# msp430g2432_uC_Module.net
KiCad netlist of a schematic drawn in EAGLE
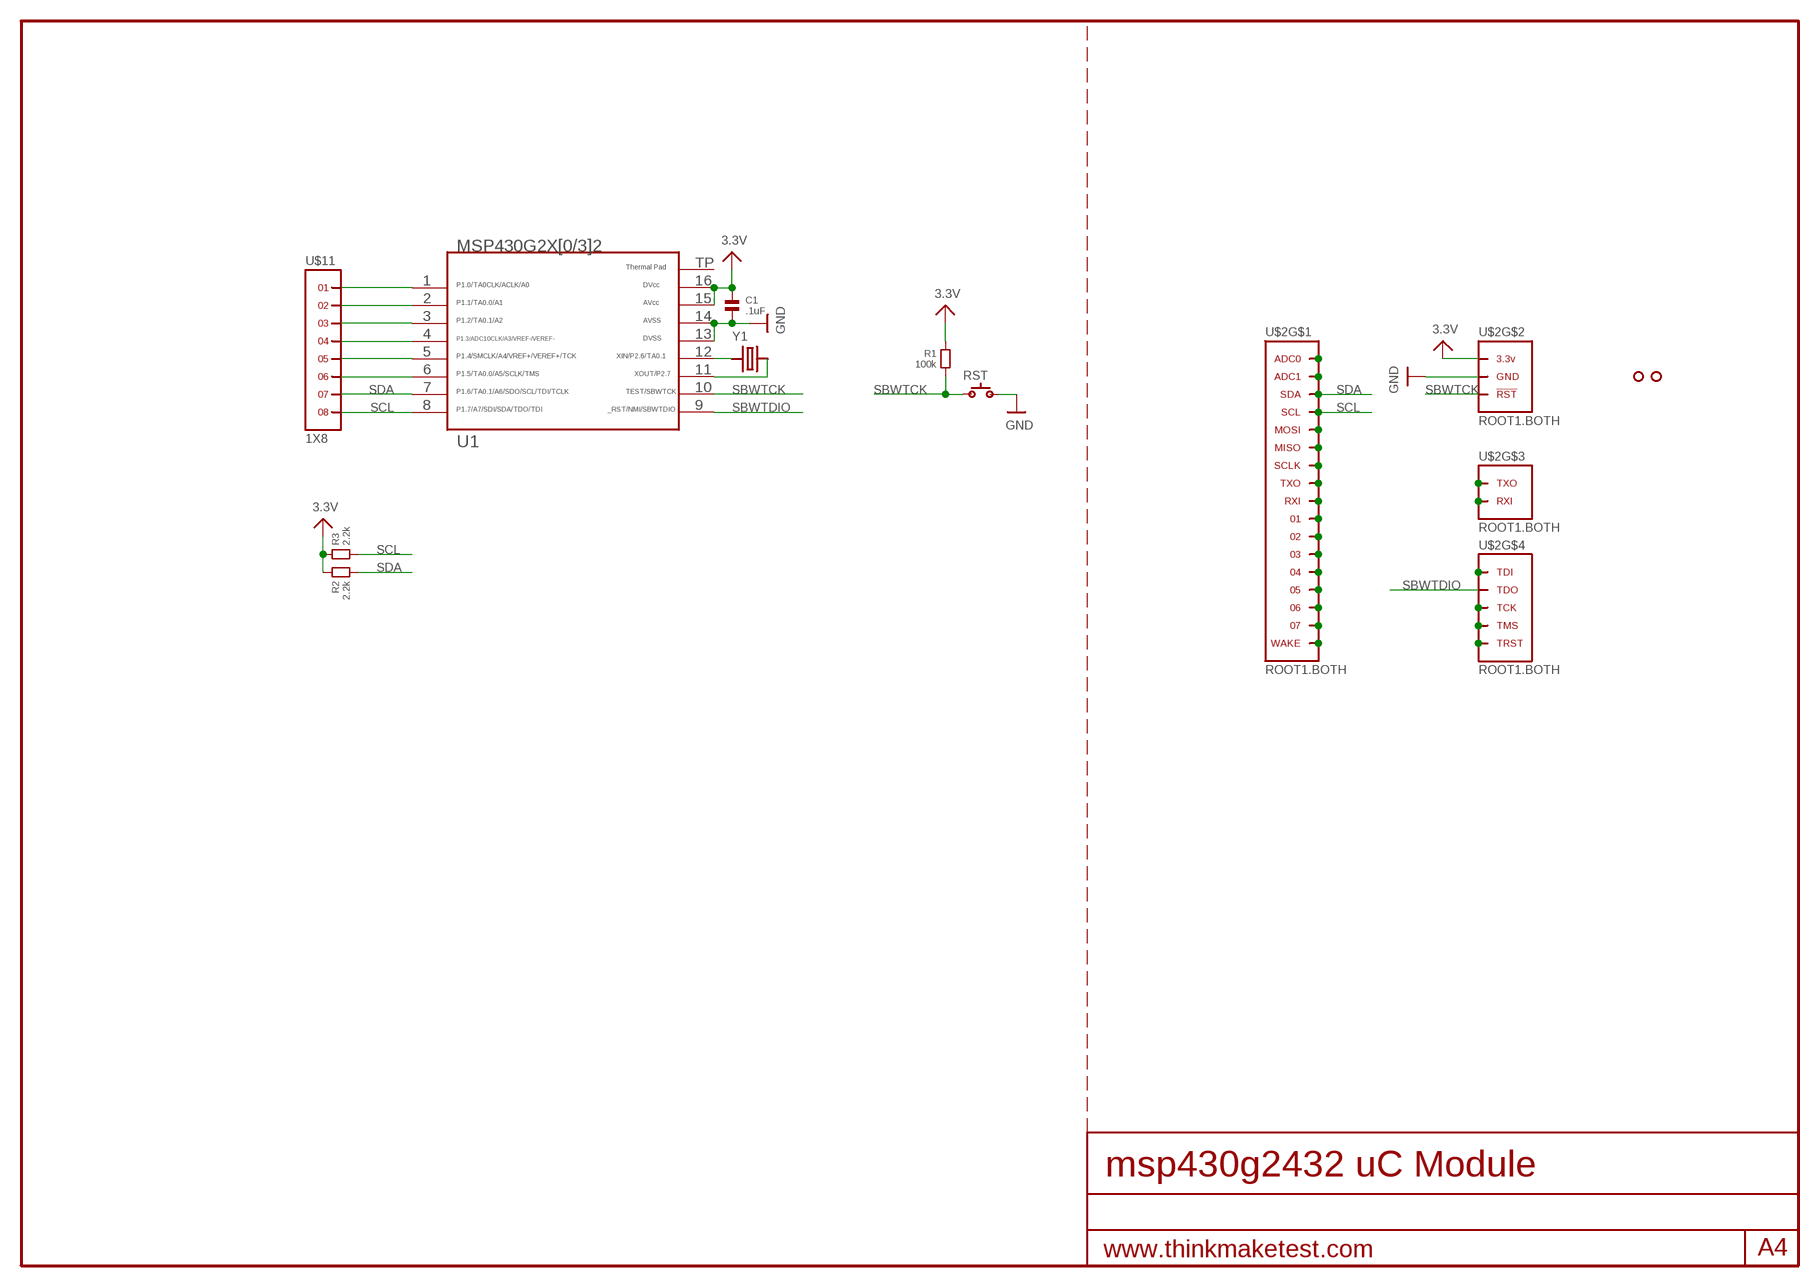
[diagram p0: schematic, sheet 1]

(export (version "E")
  (design (tool "Eeschema 10.0.6"))
  (components
    (comp (ref "C1")
      (value ".1uF")
      (footprint "eagle-import:0603")
      (libsource (lib "eagle-import") (part "CAPACITOR.0603"))
    )
    (comp (ref "R1")
      (value "100k")
      (footprint "eagle-import:0603")
      (libsource (lib "eagle-import") (part "RESISTOR.0603"))
    )
    (comp (ref "R2")
      (value "2.2k")
      (footprint "eagle-import:0603")
      (libsource (lib "eagle-import") (part "RESISTOR.0603"))
    )
    (comp (ref "R3")
      (value "2.2k")
      (footprint "eagle-import:0603")
      (libsource (lib "eagle-import") (part "RESISTOR.0603"))
    )
    (comp (ref "RST")
      (value "SPST.B3U-3000P(M)-B")
      (footprint "eagle-import:B3U-3000P(M)-B")
      (libsource (lib "eagle-import") (part "SPST.B3U-3000P(M)-B"))
    )
    (comp (ref "U$2")
      (value "ROOT1.BOTH")
      (footprint "eagle-import:ROOT1.BOTH")
      (libsource (lib "eagle-import") (part "ROOT1.BOTH"))
    )
    (comp (ref "U$3")
      (value "HOLE.2MM")
      (footprint "eagle-import:2MM")
      (libsource (lib "eagle-import") (part "HOLE.2MM"))
    )
    (comp (ref "U$4")
      (value "HOLE.2MM")
      (footprint "eagle-import:2MM")
      (libsource (lib "eagle-import") (part "HOLE.2MM"))
    )
    (comp (ref "U$11")
      (value "1X8")
      (footprint "eagle-import:1X8")
      (libsource (lib "eagle-import") (part "1X8"))
    )
    (comp (ref "U1")
      (value "G2432.QFN16")
      (footprint "eagle-import:RSA16")
      (libsource (lib "eagle-import") (part "G2X[0/3]2---RSA16"))
    )
    (comp (ref "Y1")
      (value "CRYSTAL.ABS07")
      (footprint "eagle-import:ABS07")
      (libsource (lib "eagle-import") (part "CRYSTAL.ABS07"))
    )
  )
  (nets
    (net (code "1") (name "/SBWTCK") (class "Default")
      (node (ref "R1") (pin "2") (pinfunction "2_2") (pintype "bidirectional"))
      (node (ref "RST") (pin "2") (pinfunction "2_2") (pintype "bidirectional"))
      (node (ref "U$2") (pin "RST") (pinfunction "~{RST}_RST") (pintype "bidirectional"))
      (node (ref "U$2") (pin "RST@1") (pinfunction "~{RST}_RST@1") (pintype "bidirectional"))
      (node (ref "U$2") (pin "RST@VIA") (pinfunction "~{RST}_RST@VIA") (pintype "bidirectional"))
      (node (ref "U1") (pin "10") (pinfunction "10_10") (pintype "bidirectional"))
    )
    (net (code "2") (name "/SBWTDIO") (class "Default")
      (node (ref "U$2") (pin "TDO") (pinfunction "TDO_TDO") (pintype "bidirectional"))
      (node (ref "U$2") (pin "TDO@1") (pinfunction "TDO_TDO@1") (pintype "bidirectional"))
      (node (ref "U$2") (pin "TDO@VIA") (pinfunction "TDO_TDO@VIA") (pintype "bidirectional"))
      (node (ref "U1") (pin "9") (pinfunction "9_9") (pintype "bidirectional"))
    )
    (net (code "3") (name "/SCL") (class "Default")
      (node (ref "R3") (pin "2") (pinfunction "2_2") (pintype "bidirectional"))
      (node (ref "U$11") (pin "8") (pinfunction "8_8") (pintype "bidirectional"))
      (node (ref "U$2") (pin "SCL") (pinfunction "SCL_SCL") (pintype "bidirectional"))
      (node (ref "U$2") (pin "SCL@1") (pinfunction "SCL_SCL@1") (pintype "bidirectional"))
      (node (ref "U$2") (pin "SCL@VIA") (pinfunction "SCL_SCL@VIA") (pintype "bidirectional"))
      (node (ref "U1") (pin "8") (pinfunction "8_8") (pintype "bidirectional"))
    )
    (net (code "4") (name "/SDA") (class "Default")
      (node (ref "R2") (pin "2") (pinfunction "2_2") (pintype "bidirectional"))
      (node (ref "U$11") (pin "7") (pinfunction "7_7") (pintype "bidirectional"))
      (node (ref "U$2") (pin "SDA") (pinfunction "SDA_SDA") (pintype "bidirectional"))
      (node (ref "U$2") (pin "SDA@1") (pinfunction "SDA_SDA@1") (pintype "bidirectional"))
      (node (ref "U$2") (pin "SDA@VIA") (pinfunction "SDA_SDA@VIA") (pintype "bidirectional"))
      (node (ref "U1") (pin "7") (pinfunction "7_7") (pintype "bidirectional"))
    )
    (net (code "5") (name "3.3V") (class "Default")
      (node (ref "C1") (pin "1") (pinfunction "1_1") (pintype "bidirectional"))
      (node (ref "R1") (pin "1") (pinfunction "1_1") (pintype "bidirectional"))
      (node (ref "R2") (pin "1") (pinfunction "1_1") (pintype "bidirectional"))
      (node (ref "R3") (pin "1") (pinfunction "1_1") (pintype "bidirectional"))
      (node (ref "U$2") (pin "3.3V@1") (pinfunction "3.3V_3.3V@1") (pintype "bidirectional"))
      (node (ref "U$2") (pin "3.3V@10") (pinfunction "3.3V_3.3V@10") (pintype "bidirectional"))
      (node (ref "U$2") (pin "3.3V@11") (pinfunction "3.3V_3.3V@11") (pintype "bidirectional"))
      (node (ref "U$2") (pin "3.3V@12") (pinfunction "3.3V_3.3V@12") (pintype "bidirectional"))
      (node (ref "U$2") (pin "3.3V@13") (pinfunction "3.3V_3.3V@13") (pintype "bidirectional"))
      (node (ref "U$2") (pin "3.3V@14") (pinfunction "3.3V_3.3V@14") (pintype "bidirectional"))
      (node (ref "U$2") (pin "3.3V@15") (pinfunction "3.3V_3.3V@15") (pintype "bidirectional"))
      (node (ref "U$2") (pin "3.3V@16") (pinfunction "3.3V_3.3V@16") (pintype "bidirectional"))
      (node (ref "U$2") (pin "3.3V@17") (pinfunction "3.3V_3.3V@17") (pintype "bidirectional"))
      (node (ref "U$2") (pin "3.3V@18") (pinfunction "3.3V_3.3V@18") (pintype "bidirectional"))
      (node (ref "U$2") (pin "3.3V@19") (pinfunction "3.3V_3.3V@19") (pintype "bidirectional"))
      (node (ref "U$2") (pin "3.3V@2") (pinfunction "3.3V_3.3V@2") (pintype "bidirectional"))
      (node (ref "U$2") (pin "3.3V@20") (pinfunction "3.3V_3.3V@20") (pintype "bidirectional"))
      (node (ref "U$2") (pin "3.3V@21") (pinfunction "3.3V_3.3V@21") (pintype "bidirectional"))
      (node (ref "U$2") (pin "3.3V@22") (pinfunction "3.3V_3.3V@22") (pintype "bidirectional"))
      (node (ref "U$2") (pin "3.3V@23") (pinfunction "3.3V_3.3V@23") (pintype "bidirectional"))
      (node (ref "U$2") (pin "3.3V@24") (pinfunction "3.3V_3.3V@24") (pintype "bidirectional"))
      (node (ref "U$2") (pin "3.3V@3") (pinfunction "3.3V_3.3V@3") (pintype "bidirectional"))
      (node (ref "U$2") (pin "3.3V@4") (pinfunction "3.3V_3.3V@4") (pintype "bidirectional"))
      (node (ref "U$2") (pin "3.3V@5") (pinfunction "3.3V_3.3V@5") (pintype "bidirectional"))
      (node (ref "U$2") (pin "3.3V@6") (pinfunction "3.3V_3.3V@6") (pintype "bidirectional"))
      (node (ref "U$2") (pin "3.3V@7") (pinfunction "3.3V_3.3V@7") (pintype "bidirectional"))
      (node (ref "U$2") (pin "3.3V@8") (pinfunction "3.3V_3.3V@8") (pintype "bidirectional"))
      (node (ref "U$2") (pin "3.3V@9") (pinfunction "3.3V_3.3V@9") (pintype "bidirectional"))
      (node (ref "U$2") (pin "3.3V@VIA") (pinfunction "3.3V_3.3V@VIA") (pintype "bidirectional"))
      (node (ref "U1") (pin "15") (pinfunction "15_15") (pintype "bidirectional"))
      (node (ref "U1") (pin "16") (pinfunction "16_16") (pintype "bidirectional"))
    )
    (net (code "6") (name "GND") (class "Default")
      (node (ref "C1") (pin "2") (pinfunction "2_2") (pintype "bidirectional"))
      (node (ref "RST") (pin "1") (pinfunction "1_1") (pintype "bidirectional"))
      (node (ref "U$2") (pin "GND@1") (pinfunction "GND_GND@1") (pintype "bidirectional"))
      (node (ref "U$2") (pin "GND@10") (pinfunction "GND_GND@10") (pintype "bidirectional"))
      (node (ref "U$2") (pin "GND@11") (pinfunction "GND_GND@11") (pintype "bidirectional"))
      (node (ref "U$2") (pin "GND@12") (pinfunction "GND_GND@12") (pintype "bidirectional"))
      (node (ref "U$2") (pin "GND@13") (pinfunction "GND_GND@13") (pintype "bidirectional"))
      (node (ref "U$2") (pin "GND@14") (pinfunction "GND_GND@14") (pintype "bidirectional"))
      (node (ref "U$2") (pin "GND@15") (pinfunction "GND_GND@15") (pintype "bidirectional"))
      (node (ref "U$2") (pin "GND@16") (pinfunction "GND_GND@16") (pintype "bidirectional"))
      (node (ref "U$2") (pin "GND@17") (pinfunction "GND_GND@17") (pintype "bidirectional"))
      (node (ref "U$2") (pin "GND@18") (pinfunction "GND_GND@18") (pintype "bidirectional"))
      (node (ref "U$2") (pin "GND@19") (pinfunction "GND_GND@19") (pintype "bidirectional"))
      (node (ref "U$2") (pin "GND@2") (pinfunction "GND_GND@2") (pintype "bidirectional"))
      (node (ref "U$2") (pin "GND@20") (pinfunction "GND_GND@20") (pintype "bidirectional"))
      (node (ref "U$2") (pin "GND@21") (pinfunction "GND_GND@21") (pintype "bidirectional"))
      (node (ref "U$2") (pin "GND@22") (pinfunction "GND_GND@22") (pintype "bidirectional"))
      (node (ref "U$2") (pin "GND@23") (pinfunction "GND_GND@23") (pintype "bidirectional"))
      (node (ref "U$2") (pin "GND@24") (pinfunction "GND_GND@24") (pintype "bidirectional"))
      (node (ref "U$2") (pin "GND@25") (pinfunction "GND_GND@25") (pintype "bidirectional"))
      (node (ref "U$2") (pin "GND@26") (pinfunction "GND_GND@26") (pintype "bidirectional"))
      (node (ref "U$2") (pin "GND@3") (pinfunction "GND_GND@3") (pintype "bidirectional"))
      (node (ref "U$2") (pin "GND@4") (pinfunction "GND_GND@4") (pintype "bidirectional"))
      (node (ref "U$2") (pin "GND@5") (pinfunction "GND_GND@5") (pintype "bidirectional"))
      (node (ref "U$2") (pin "GND@6") (pinfunction "GND_GND@6") (pintype "bidirectional"))
      (node (ref "U$2") (pin "GND@7") (pinfunction "GND_GND@7") (pintype "bidirectional"))
      (node (ref "U$2") (pin "GND@8") (pinfunction "GND_GND@8") (pintype "bidirectional"))
      (node (ref "U$2") (pin "GND@9") (pinfunction "GND_GND@9") (pintype "bidirectional"))
      (node (ref "U$2") (pin "GND@VIA") (pinfunction "GND_GND@VIA") (pintype "bidirectional"))
      (node (ref "U1") (pin "13") (pinfunction "13_13") (pintype "bidirectional"))
      (node (ref "U1") (pin "14") (pinfunction "14_14") (pintype "bidirectional"))
    )
    (net (code "7") (name "Net-(U$2-Pad01)") (class "Default")
      (node (ref "U$2") (pin "01") (pinfunction "01_01") (pintype "bidirectional"))
      (node (ref "U$2") (pin "01@1") (pinfunction "01_01@1") (pintype "bidirectional"))
      (node (ref "U$2") (pin "01@VIA") (pinfunction "01_01@VIA") (pintype "bidirectional"))
    )
    (net (code "8") (name "Net-(U$2-Pad02)") (class "Default")
      (node (ref "U$2") (pin "02") (pinfunction "02_02") (pintype "bidirectional"))
      (node (ref "U$2") (pin "02@1") (pinfunction "02_02@1") (pintype "bidirectional"))
      (node (ref "U$2") (pin "02@VIA") (pinfunction "02_02@VIA") (pintype "bidirectional"))
    )
    (net (code "9") (name "Net-(U$2-Pad03)") (class "Default")
      (node (ref "U$2") (pin "03") (pinfunction "03_03") (pintype "bidirectional"))
      (node (ref "U$2") (pin "03@1") (pinfunction "03_03@1") (pintype "bidirectional"))
      (node (ref "U$2") (pin "03@VIA") (pinfunction "03_03@VIA") (pintype "bidirectional"))
    )
    (net (code "10") (name "Net-(U$2-Pad04)") (class "Default")
      (node (ref "U$2") (pin "04") (pinfunction "04_04") (pintype "bidirectional"))
      (node (ref "U$2") (pin "04@1") (pinfunction "04_04@1") (pintype "bidirectional"))
      (node (ref "U$2") (pin "04@VIA") (pinfunction "04_04@VIA") (pintype "bidirectional"))
    )
    (net (code "11") (name "Net-(U$2-Pad05)") (class "Default")
      (node (ref "U$2") (pin "05") (pinfunction "05_05") (pintype "bidirectional"))
      (node (ref "U$2") (pin "05@1") (pinfunction "05_05@1") (pintype "bidirectional"))
      (node (ref "U$2") (pin "05@VIA") (pinfunction "05_05@VIA") (pintype "bidirectional"))
    )
    (net (code "12") (name "Net-(U$2-Pad06)") (class "Default")
      (node (ref "U$2") (pin "06") (pinfunction "06_06") (pintype "bidirectional"))
      (node (ref "U$2") (pin "06@1") (pinfunction "06_06@1") (pintype "bidirectional"))
      (node (ref "U$2") (pin "06@VIA") (pinfunction "06_06@VIA") (pintype "bidirectional"))
    )
    (net (code "13") (name "Net-(U$2-Pad07)") (class "Default")
      (node (ref "U$2") (pin "07") (pinfunction "07_07") (pintype "bidirectional"))
      (node (ref "U$2") (pin "07@1") (pinfunction "07_07@1") (pintype "bidirectional"))
      (node (ref "U$2") (pin "07@VIA") (pinfunction "07_07@VIA") (pintype "bidirectional"))
    )
    (net (code "14") (name "Net-(U$2-PadADC0)") (class "Default")
      (node (ref "U$2") (pin "ADC0") (pinfunction "ADC0_ADC0") (pintype "bidirectional"))
      (node (ref "U$2") (pin "ADC0@1") (pinfunction "ADC0_ADC0@1") (pintype "bidirectional"))
      (node (ref "U$2") (pin "ADC0@VIA") (pinfunction "ADC0_ADC0@VIA") (pintype "bidirectional"))
    )
    (net (code "15") (name "Net-(U$2-PadADC1)") (class "Default")
      (node (ref "U$2") (pin "ADC1") (pinfunction "ADC1_ADC1") (pintype "bidirectional"))
      (node (ref "U$2") (pin "ADC1@1") (pinfunction "ADC1_ADC1@1") (pintype "bidirectional"))
      (node (ref "U$2") (pin "ADC1@VIA") (pinfunction "ADC1_ADC1@VIA") (pintype "bidirectional"))
    )
    (net (code "16") (name "Net-(U$2-PadMISO)") (class "Default")
      (node (ref "U$2") (pin "MISO") (pinfunction "MISO_MISO") (pintype "bidirectional"))
      (node (ref "U$2") (pin "MISO@1") (pinfunction "MISO_MISO@1") (pintype "bidirectional"))
      (node (ref "U$2") (pin "MISO@VIA") (pinfunction "MISO_MISO@VIA") (pintype "bidirectional"))
    )
    (net (code "17") (name "Net-(U$2-PadMOSI)") (class "Default")
      (node (ref "U$2") (pin "MOSI") (pinfunction "MOSI_MOSI") (pintype "bidirectional"))
      (node (ref "U$2") (pin "MOSI@1") (pinfunction "MOSI_MOSI@1") (pintype "bidirectional"))
      (node (ref "U$2") (pin "MOSI@VIA") (pinfunction "MOSI_MOSI@VIA") (pintype "bidirectional"))
    )
    (net (code "18") (name "Net-(U$2-PadRXI)") (class "Default")
      (node (ref "U$2") (pin "RXI") (pinfunction "RXI_RXI") (pintype "bidirectional"))
      (node (ref "U$2") (pin "RXI@1") (pinfunction "RXI_RXI@1") (pintype "bidirectional"))
      (node (ref "U$2") (pin "RXI@VIA") (pinfunction "RXI_RXI@VIA") (pintype "bidirectional"))
    )
    (net (code "19") (name "Net-(U$2-PadSCLK)") (class "Default")
      (node (ref "U$2") (pin "SCLK") (pinfunction "SCLK_SCLK") (pintype "bidirectional"))
      (node (ref "U$2") (pin "SCLK@1") (pinfunction "SCLK_SCLK@1") (pintype "bidirectional"))
      (node (ref "U$2") (pin "SCLK@VIA") (pinfunction "SCLK_SCLK@VIA") (pintype "bidirectional"))
    )
    (net (code "20") (name "Net-(U$2-PadTCK)") (class "Default")
      (node (ref "U$2") (pin "TCK") (pinfunction "TCK_TCK") (pintype "bidirectional"))
      (node (ref "U$2") (pin "TCK@1") (pinfunction "TCK_TCK@1") (pintype "bidirectional"))
      (node (ref "U$2") (pin "TCK@VIA") (pinfunction "TCK_TCK@VIA") (pintype "bidirectional"))
    )
    (net (code "21") (name "Net-(U$2-PadTDI)") (class "Default")
      (node (ref "U$2") (pin "TDI") (pinfunction "TDI_TDI") (pintype "bidirectional"))
      (node (ref "U$2") (pin "TDI@1") (pinfunction "TDI_TDI@1") (pintype "bidirectional"))
      (node (ref "U$2") (pin "TDI@VIA") (pinfunction "TDI_TDI@VIA") (pintype "bidirectional"))
    )
    (net (code "22") (name "Net-(U$2-PadTMS)") (class "Default")
      (node (ref "U$2") (pin "TMS") (pinfunction "TMS_TMS") (pintype "bidirectional"))
      (node (ref "U$2") (pin "TMS@1") (pinfunction "TMS_TMS@1") (pintype "bidirectional"))
      (node (ref "U$2") (pin "TMS@VIA") (pinfunction "TMS_TMS@VIA") (pintype "bidirectional"))
    )
    (net (code "23") (name "Net-(U$2-PadTRST)") (class "Default")
      (node (ref "U$2") (pin "TRST") (pinfunction "TRST_TRST") (pintype "bidirectional"))
      (node (ref "U$2") (pin "TRST@1") (pinfunction "TRST_TRST@1") (pintype "bidirectional"))
      (node (ref "U$2") (pin "TRST@VIA") (pinfunction "TRST_TRST@VIA") (pintype "bidirectional"))
    )
    (net (code "24") (name "Net-(U$2-PadTXO)") (class "Default")
      (node (ref "U$2") (pin "TXO") (pinfunction "TXO_TXO") (pintype "bidirectional"))
      (node (ref "U$2") (pin "TXO@1") (pinfunction "TXO_TXO@1") (pintype "bidirectional"))
      (node (ref "U$2") (pin "TXO@VIA") (pinfunction "TXO_TXO@VIA") (pintype "bidirectional"))
    )
    (net (code "25") (name "Net-(U$2-PadWAKE)") (class "Default")
      (node (ref "U$2") (pin "WAKE") (pinfunction "WAKE_WAKE") (pintype "bidirectional"))
      (node (ref "U$2") (pin "WAKE@1") (pinfunction "WAKE_WAKE@1") (pintype "bidirectional"))
      (node (ref "U$2") (pin "WAKE@VIA") (pinfunction "WAKE_WAKE@VIA") (pintype "bidirectional"))
    )
    (net (code "26") (name "Net-(U$2C-RXI-PadRXI.DBG)") (class "Default")
      (node (ref "U$2") (pin "RXI.DBG") (pinfunction "RXI_RXI.DBG") (pintype "bidirectional"))
      (node (ref "U$2") (pin "RXI.DBG@1") (pinfunction "RXI_RXI.DBG@1") (pintype "bidirectional"))
      (node (ref "U$2") (pin "RXI.DBG@VIA") (pinfunction "RXI_RXI.DBG@VIA") (pintype "bidirectional"))
    )
    (net (code "27") (name "Net-(U$2C-TXO-PadTXO.DBG)") (class "Default")
      (node (ref "U$2") (pin "TXO.DBG") (pinfunction "TXO_TXO.DBG") (pintype "bidirectional"))
      (node (ref "U$2") (pin "TXO.DBG@1") (pinfunction "TXO_TXO.DBG@1") (pintype "bidirectional"))
      (node (ref "U$2") (pin "TXO.DBG@VIA") (pinfunction "TXO_TXO.DBG@VIA") (pintype "bidirectional"))
    )
    (net (code "28") (name "Net-(U$11-Pad1)") (class "Default")
      (node (ref "U$11") (pin "1") (pinfunction "1_1") (pintype "bidirectional"))
      (node (ref "U1") (pin "1") (pinfunction "1_1") (pintype "bidirectional"))
    )
    (net (code "29") (name "Net-(U$11-Pad2)") (class "Default")
      (node (ref "U$11") (pin "2") (pinfunction "2_2") (pintype "bidirectional"))
      (node (ref "U1") (pin "2") (pinfunction "2_2") (pintype "bidirectional"))
    )
    (net (code "30") (name "Net-(U$11-Pad3)") (class "Default")
      (node (ref "U$11") (pin "3") (pinfunction "3_3") (pintype "bidirectional"))
      (node (ref "U1") (pin "3") (pinfunction "3_3") (pintype "bidirectional"))
    )
    (net (code "31") (name "Net-(U$11-Pad4)") (class "Default")
      (node (ref "U$11") (pin "4") (pinfunction "4_4") (pintype "bidirectional"))
      (node (ref "U1") (pin "4") (pinfunction "4_4") (pintype "bidirectional"))
    )
    (net (code "32") (name "Net-(U$11-Pad5)") (class "Default")
      (node (ref "U$11") (pin "5") (pinfunction "5_5") (pintype "bidirectional"))
      (node (ref "U1") (pin "5") (pinfunction "5_5") (pintype "bidirectional"))
    )
    (net (code "33") (name "Net-(U$11-Pad6)") (class "Default")
      (node (ref "U$11") (pin "6") (pinfunction "6_6") (pintype "bidirectional"))
      (node (ref "U1") (pin "6") (pinfunction "6_6") (pintype "bidirectional"))
    )
    (net (code "34") (name "Net-(U1-Pad11)") (class "Default")
      (node (ref "U1") (pin "11") (pinfunction "11_11") (pintype "bidirectional"))
      (node (ref "Y1") (pin "2") (pinfunction "2_2") (pintype "passive"))
    )
    (net (code "35") (name "Net-(U1-Pad12)") (class "Default")
      (node (ref "U1") (pin "12") (pinfunction "12_12") (pintype "bidirectional"))
      (node (ref "Y1") (pin "1") (pinfunction "1_1") (pintype "passive"))
    )
    (net (code "36") (name "unconnected-(U1-PadTP)") (class "Default")
      (node (ref "U1") (pin "TP") (pinfunction "TP_TP") (pintype "bidirectional"))
    )
  )
)
